# Power.net
KiCad netlist of a schematic drawn in Altium Designer
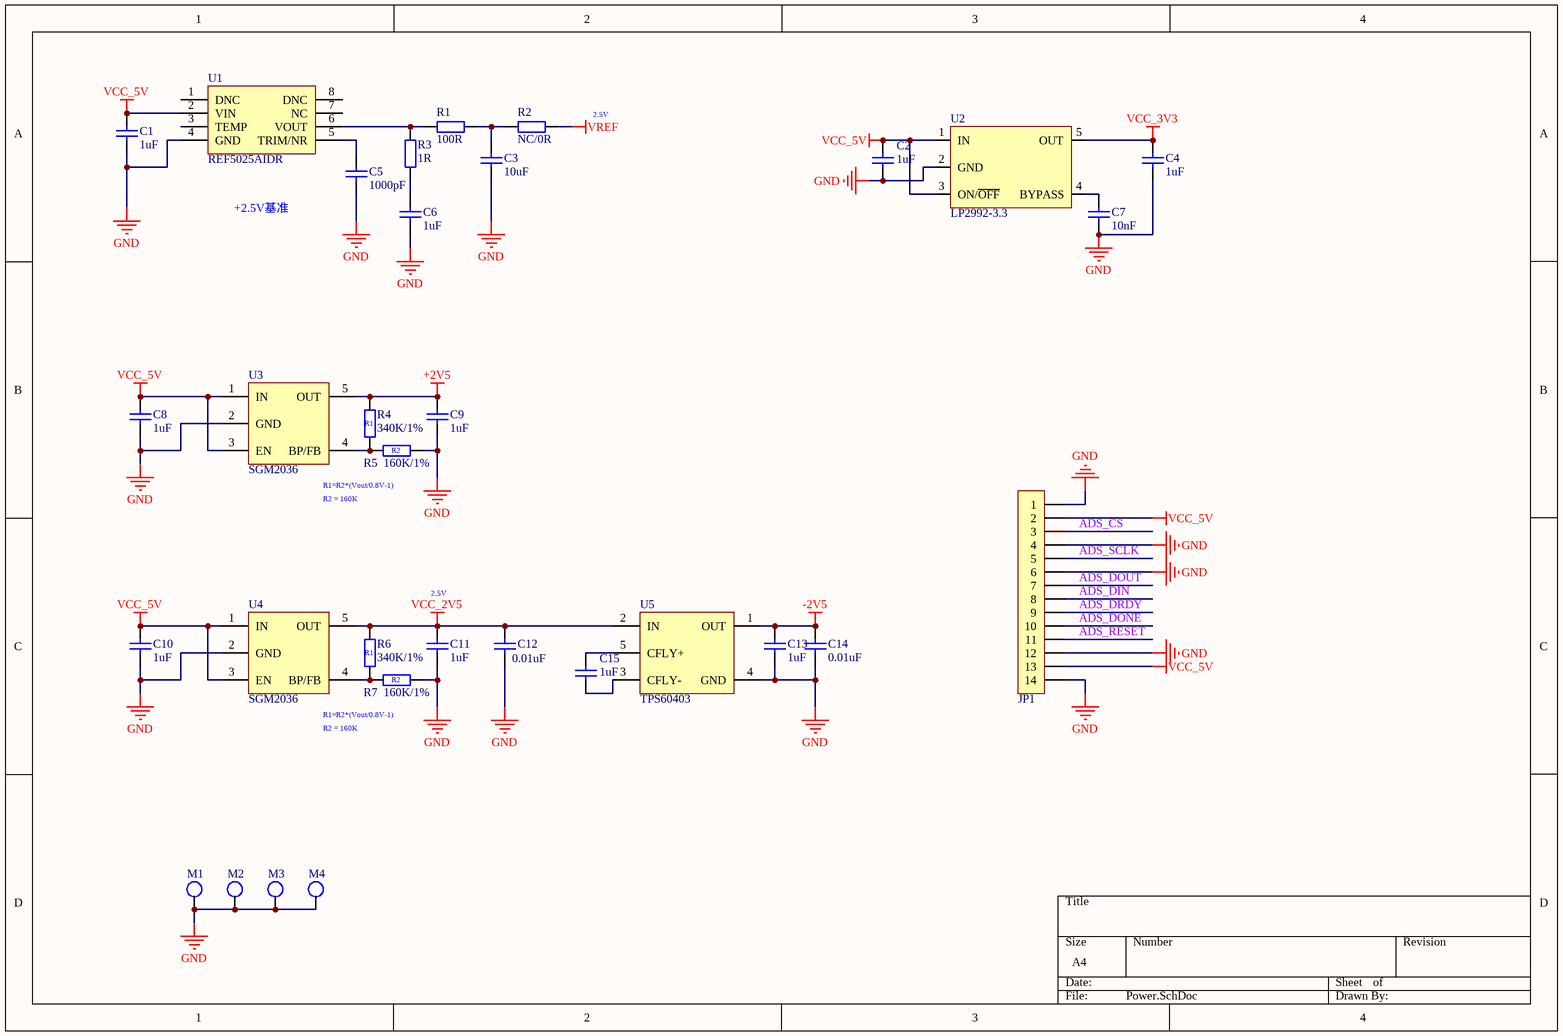
[diagram p0: Power.SchDoc]

(export (version "E")
  (design (tool "Eeschema 10.0.6"))
  (components
    (comp (ref "C1")
      (value "1uF")
      (footprint "C0402_L")
      (description "贴片电容")
      (libsource (lib "0.1 - 电阻-电容-电感-晶振-晶体-磁珠-电位器") (part "C"))
    )
    (comp (ref "C2")
      (value "1uF")
      (footprint "C0402_L")
      (description "贴片电容")
      (libsource (lib "0.1 - 电阻-电容-电感-晶振-晶体-磁珠-电位器") (part "C"))
    )
    (comp (ref "C3")
      (value "10uF")
      (footprint "C0603_L")
      (description "贴片电容")
      (libsource (lib "0.1 - 电阻-电容-电感-晶振-晶体-磁珠-电位器") (part "C"))
    )
    (comp (ref "C4")
      (value "1uF")
      (footprint "C0402_L")
      (description "贴片电容")
      (libsource (lib "0.1 - 电阻-电容-电感-晶振-晶体-磁珠-电位器") (part "C"))
    )
    (comp (ref "C5")
      (value "1000pF")
      (footprint "C0402_L")
      (description "贴片电容")
      (libsource (lib "0.1 - 电阻-电容-电感-晶振-晶体-磁珠-电位器") (part "C"))
    )
    (comp (ref "C6")
      (value "1uF")
      (footprint "C0402_L")
      (description "贴片电容")
      (libsource (lib "0.1 - 电阻-电容-电感-晶振-晶体-磁珠-电位器") (part "C"))
    )
    (comp (ref "C7")
      (value "10nF")
      (footprint "C0402_L")
      (description "贴片电容")
      (libsource (lib "0.1 - 电阻-电容-电感-晶振-晶体-磁珠-电位器") (part "C"))
    )
    (comp (ref "C8")
      (value "1uF")
      (footprint "C0402_L")
      (description "贴片电容")
      (libsource (lib "0.1 - 电阻-电容-电感-晶振-晶体-磁珠-电位器") (part "C"))
    )
    (comp (ref "C9")
      (value "1uF")
      (footprint "C0402_L")
      (description "贴片电容")
      (libsource (lib "0.1 - 电阻-电容-电感-晶振-晶体-磁珠-电位器") (part "C"))
    )
    (comp (ref "C10")
      (value "1uF")
      (footprint "C0402_L")
      (description "贴片电容")
      (libsource (lib "0.1 - 电阻-电容-电感-晶振-晶体-磁珠-电位器") (part "C"))
    )
    (comp (ref "C11")
      (value "1uF")
      (footprint "C0402_L")
      (description "贴片电容")
      (libsource (lib "0.1 - 电阻-电容-电感-晶振-晶体-磁珠-电位器") (part "C"))
    )
    (comp (ref "C12")
      (value "0.01uF")
      (footprint "C0402_L")
      (description "贴片电容")
      (libsource (lib "0.1 - 电阻-电容-电感-晶振-晶体-磁珠-电位器") (part "C"))
    )
    (comp (ref "C13")
      (value "1uF")
      (footprint "C0402_L")
      (description "贴片电容")
      (libsource (lib "0.1 - 电阻-电容-电感-晶振-晶体-磁珠-电位器") (part "C"))
    )
    (comp (ref "C14")
      (value "0.01uF")
      (footprint "C0402_L")
      (description "贴片电容")
      (libsource (lib "0.1 - 电阻-电容-电感-晶振-晶体-磁珠-电位器") (part "C"))
    )
    (comp (ref "C15")
      (value "1uF")
      (footprint "C0402_L")
      (description "贴片电容")
      (libsource (lib "0.1 - 电阻-电容-电感-晶振-晶体-磁珠-电位器") (part "C"))
    )
    (comp (ref "JP1")
      (value "HDR-1X14")
      (footprint "FPC0.5-WT-14P")
      (description "14P接插件")
      (libsource (lib "5.5 - 2.54mm(100mil)连接器(XH2.54)") (part "Header 14"))
    )
    (comp (ref "M1")
      (value "M2")
      (footprint "M2")
      (description "M2孔支撑柱")
      (libsource (lib "USER_Lib") (part "M2系列"))
    )
    (comp (ref "M2")
      (value "M2")
      (footprint "M2")
      (description "M2孔支撑柱")
      (libsource (lib "USER_Lib") (part "M2系列"))
    )
    (comp (ref "M3")
      (value "M2")
      (footprint "M2")
      (description "M2孔支撑柱")
      (libsource (lib "USER_Lib") (part "M2系列"))
    )
    (comp (ref "M4")
      (value "M2")
      (footprint "M2")
      (description "M2孔支撑柱")
      (libsource (lib "USER_Lib") (part "M2系列"))
    )
    (comp (ref "R1")
      (value "100R")
      (footprint "R0402_L")
      (description "贴片电阻")
      (libsource (lib "0.1 - 电阻-电容-电感-晶振-晶体-磁珠-电位器") (part "R"))
    )
    (comp (ref "R2")
      (value "NC/0R")
      (footprint "R0402_L")
      (description "贴片电阻")
      (libsource (lib "0.1 - 电阻-电容-电感-晶振-晶体-磁珠-电位器") (part "R"))
    )
    (comp (ref "R3")
      (value "1R")
      (footprint "R0402_L")
      (description "贴片电阻")
      (libsource (lib "0.1 - 电阻-电容-电感-晶振-晶体-磁珠-电位器") (part "R"))
    )
    (comp (ref "R4")
      (value "340K/1%")
      (footprint "R0402_L")
      (description "贴片电阻")
      (libsource (lib "0.1 - 电阻-电容-电感-晶振-晶体-磁珠-电位器") (part "R"))
    )
    (comp (ref "R5")
      (value "160K/1%")
      (footprint "R0402_L")
      (description "贴片电阻")
      (libsource (lib "0.1 - 电阻-电容-电感-晶振-晶体-磁珠-电位器") (part "R"))
    )
    (comp (ref "R6")
      (value "340K/1%")
      (footprint "R0402_L")
      (description "贴片电阻")
      (libsource (lib "0.1 - 电阻-电容-电感-晶振-晶体-磁珠-电位器") (part "R"))
    )
    (comp (ref "R7")
      (value "160K/1%")
      (footprint "R0402_L")
      (description "贴片电阻")
      (libsource (lib "0.1 - 电阻-电容-电感-晶振-晶体-磁珠-电位器") (part "R"))
    )
    (comp (ref "U1")
      (value "REF5025AIDR")
      (footprint "SOIC-8L")
      (description "3uVpp/V噪声 3ppm/℃漂移 电压基准 0.05%")
      (libsource (lib "USER_Lib") (part "REF5025AIDR"))
    )
    (comp (ref "U2") (value "LP2992-3.3") (footprint "SOT23-5L") (libsource (lib "USER_Lib") (part "LP2992")))
    (comp (ref "U3")
      (value "SGM2036")
      (footprint "SOT23-5L")
      (description "可调LDO")
      (libsource (lib "USER_Lib") (part "SGM2036"))
    )
    (comp (ref "U4")
      (value "SGM2036")
      (footprint "SOT23-5L")
      (description "可调LDO")
      (libsource (lib "USER_Lib") (part "SGM2036"))
    )
    (comp (ref "U5")
      (value "TPS60403")
      (footprint "SOT23-5L")
      (description "非稳压60mA电荷泵电压逆变器")
      (libsource (lib "USER_Lib") (part "TPS6040x"))
    )
  )
  (nets
    (net (code "1") (name "+2V5") (class "Default")
      (node (ref "C9") (pin "2") (pinfunction "2_2") (pintype "passive"))
      (node (ref "R4") (pin "2") (pinfunction "2_2") (pintype "passive"))
      (node (ref "U3") (pin "5") (pinfunction "OUT_5") (pintype "passive"))
    )
    (net (code "2") (name "-2V5") (class "Default")
      (node (ref "C13") (pin "2") (pinfunction "2_2") (pintype "passive"))
      (node (ref "C14") (pin "2") (pinfunction "2_2") (pintype "passive"))
      (node (ref "U5") (pin "1") (pinfunction "OUT_1") (pintype "passive"))
    )
    (net (code "3") (name "/ADS_CS") (class "Default")
      (node (ref "JP1") (pin "3") (pinfunction "3_3") (pintype "passive"))
    )
    (net (code "4") (name "/ADS_DIN") (class "Default")
      (node (ref "JP1") (pin "8") (pinfunction "8_8") (pintype "passive"))
    )
    (net (code "5") (name "/ADS_DONE") (class "Default")
      (node (ref "JP1") (pin "10") (pinfunction "10_10") (pintype "passive"))
    )
    (net (code "6") (name "/ADS_DOUT") (class "Default")
      (node (ref "JP1") (pin "7") (pinfunction "7_7") (pintype "passive"))
    )
    (net (code "7") (name "/ADS_DRDY") (class "Default")
      (node (ref "JP1") (pin "9") (pinfunction "9_9") (pintype "passive"))
    )
    (net (code "8") (name "/ADS_RESET") (class "Default")
      (node (ref "JP1") (pin "11") (pinfunction "11_11") (pintype "passive"))
    )
    (net (code "9") (name "/ADS_SCLK") (class "Default")
      (node (ref "JP1") (pin "5") (pinfunction "5_5") (pintype "passive"))
    )
    (net (code "10") (name "GND") (class "Default")
      (node (ref "C1") (pin "1") (pinfunction "1_1") (pintype "passive"))
      (node (ref "C10") (pin "1") (pinfunction "1_1") (pintype "passive"))
      (node (ref "C11") (pin "1") (pinfunction "1_1") (pintype "passive"))
      (node (ref "C12") (pin "1") (pinfunction "1_1") (pintype "passive"))
      (node (ref "C13") (pin "1") (pinfunction "1_1") (pintype "passive"))
      (node (ref "C14") (pin "1") (pinfunction "1_1") (pintype "passive"))
      (node (ref "C2") (pin "1") (pinfunction "1_1") (pintype "passive"))
      (node (ref "C3") (pin "1") (pinfunction "1_1") (pintype "passive"))
      (node (ref "C4") (pin "1") (pinfunction "1_1") (pintype "passive"))
      (node (ref "C5") (pin "1") (pinfunction "1_1") (pintype "passive"))
      (node (ref "C6") (pin "1") (pinfunction "1_1") (pintype "passive"))
      (node (ref "C7") (pin "1") (pinfunction "1_1") (pintype "passive"))
      (node (ref "C8") (pin "1") (pinfunction "1_1") (pintype "passive"))
      (node (ref "C9") (pin "1") (pinfunction "1_1") (pintype "passive"))
      (node (ref "JP1") (pin "1") (pinfunction "1_1") (pintype "passive"))
      (node (ref "JP1") (pin "12") (pinfunction "12_12") (pintype "passive"))
      (node (ref "JP1") (pin "14") (pinfunction "14_14") (pintype "passive"))
      (node (ref "JP1") (pin "4") (pinfunction "4_4") (pintype "passive"))
      (node (ref "JP1") (pin "6") (pinfunction "6_6") (pintype "passive"))
      (node (ref "M1") (pin "1") (pinfunction "1_1") (pintype "passive"))
      (node (ref "M2") (pin "1") (pinfunction "1_1") (pintype "passive"))
      (node (ref "M3") (pin "1") (pinfunction "1_1") (pintype "passive"))
      (node (ref "M4") (pin "1") (pinfunction "1_1") (pintype "passive"))
      (node (ref "R5") (pin "2") (pinfunction "2_2") (pintype "passive"))
      (node (ref "R7") (pin "2") (pinfunction "2_2") (pintype "passive"))
      (node (ref "U1") (pin "4") (pinfunction "GND_4") (pintype "passive"))
      (node (ref "U2") (pin "2") (pinfunction "GND_2") (pintype "passive"))
      (node (ref "U3") (pin "2") (pinfunction "GND_2") (pintype "passive"))
      (node (ref "U4") (pin "2") (pinfunction "GND_2") (pintype "passive"))
      (node (ref "U5") (pin "4") (pinfunction "GND_4") (pintype "passive"))
    )
    (net (code "11") (name "Net-(C3-Pad2)") (class "Default")
      (node (ref "C3") (pin "2") (pinfunction "2_2") (pintype "passive"))
      (node (ref "R1") (pin "2") (pinfunction "2_2") (pintype "passive"))
      (node (ref "R2") (pin "1") (pinfunction "1_1") (pintype "passive"))
    )
    (net (code "12") (name "Net-(C6-Pad2)") (class "Default")
      (node (ref "C6") (pin "2") (pinfunction "2_2") (pintype "passive"))
      (node (ref "R3") (pin "1") (pinfunction "1_1") (pintype "passive"))
    )
    (net (code "13") (name "Net-(U1-TRIM{slash}NR)") (class "Default")
      (node (ref "C5") (pin "2") (pinfunction "2_2") (pintype "passive"))
      (node (ref "U1") (pin "5") (pinfunction "TRIM/NR_5") (pintype "passive"))
    )
    (net (code "14") (name "Net-(U1-VOUT)") (class "Default")
      (node (ref "R1") (pin "1") (pinfunction "1_1") (pintype "passive"))
      (node (ref "R3") (pin "2") (pinfunction "2_2") (pintype "passive"))
      (node (ref "U1") (pin "6") (pinfunction "VOUT_6") (pintype "passive"))
    )
    (net (code "15") (name "Net-(U2-BYPASS)") (class "Default")
      (node (ref "C7") (pin "2") (pinfunction "2_2") (pintype "passive"))
      (node (ref "U2") (pin "4") (pinfunction "BYPASS_4") (pintype "passive"))
    )
    (net (code "16") (name "Net-(U3-BP{slash}FB)") (class "Default")
      (node (ref "R4") (pin "1") (pinfunction "1_1") (pintype "passive"))
      (node (ref "R5") (pin "1") (pinfunction "1_1") (pintype "passive"))
      (node (ref "U3") (pin "4") (pinfunction "BP/FB_4") (pintype "passive"))
    )
    (net (code "17") (name "Net-(U4-BP{slash}FB)") (class "Default")
      (node (ref "R6") (pin "1") (pinfunction "1_1") (pintype "passive"))
      (node (ref "R7") (pin "1") (pinfunction "1_1") (pintype "passive"))
      (node (ref "U4") (pin "4") (pinfunction "BP/FB_4") (pintype "passive"))
    )
    (net (code "18") (name "Net-(U5-CFLY+)") (class "Default")
      (node (ref "C15") (pin "2") (pinfunction "2_2") (pintype "passive"))
      (node (ref "U5") (pin "5") (pinfunction "CFLY+_5") (pintype "passive"))
    )
    (net (code "19") (name "Net-(U5-CFLY-)") (class "Default")
      (node (ref "C15") (pin "1") (pinfunction "1_1") (pintype "passive"))
      (node (ref "U5") (pin "3") (pinfunction "CFLY-_3") (pintype "passive"))
    )
    (net (code "20") (name "VCC_2V5") (class "Default")
      (node (ref "C11") (pin "2") (pinfunction "2_2") (pintype "passive"))
      (node (ref "C12") (pin "2") (pinfunction "2_2") (pintype "passive"))
      (node (ref "R6") (pin "2") (pinfunction "2_2") (pintype "passive"))
      (node (ref "U4") (pin "5") (pinfunction "OUT_5") (pintype "passive"))
      (node (ref "U5") (pin "2") (pinfunction "IN_2") (pintype "passive"))
    )
    (net (code "21") (name "VCC_3V3") (class "Default")
      (node (ref "C4") (pin "2") (pinfunction "2_2") (pintype "passive"))
      (node (ref "U2") (pin "5") (pinfunction "OUT_5") (pintype "passive"))
    )
    (net (code "22") (name "VCC_5V") (class "Default")
      (node (ref "C1") (pin "2") (pinfunction "2_2") (pintype "passive"))
      (node (ref "C10") (pin "2") (pinfunction "2_2") (pintype "passive"))
      (node (ref "C2") (pin "2") (pinfunction "2_2") (pintype "passive"))
      (node (ref "C8") (pin "2") (pinfunction "2_2") (pintype "passive"))
      (node (ref "JP1") (pin "13") (pinfunction "13_13") (pintype "passive"))
      (node (ref "JP1") (pin "2") (pinfunction "2_2") (pintype "passive"))
      (node (ref "U1") (pin "2") (pinfunction "VIN_2") (pintype "passive"))
      (node (ref "U2") (pin "1") (pinfunction "IN_1") (pintype "passive"))
      (node (ref "U2") (pin "3") (pinfunction "ON/~{OFF}_3") (pintype "passive"))
      (node (ref "U3") (pin "1") (pinfunction "IN_1") (pintype "passive"))
      (node (ref "U3") (pin "3") (pinfunction "EN_3") (pintype "passive"))
      (node (ref "U4") (pin "1") (pinfunction "IN_1") (pintype "passive"))
      (node (ref "U4") (pin "3") (pinfunction "EN_3") (pintype "passive"))
    )
    (net (code "23") (name "VREF") (class "Default")
      (node (ref "R2") (pin "2") (pinfunction "2_2") (pintype "passive"))
    )
    (net (code "24") (name "unconnected-(U1-DNC-Pad1)") (class "Default")
      (node (ref "U1") (pin "1") (pinfunction "DNC_1") (pintype "passive"))
    )
    (net (code "25") (name "unconnected-(U1-DNC-Pad8)") (class "Default")
      (node (ref "U1") (pin "8") (pinfunction "DNC_8") (pintype "passive"))
    )
    (net (code "26") (name "unconnected-(U1-NC-Pad7)") (class "Default")
      (node (ref "U1") (pin "7") (pinfunction "NC_7") (pintype "passive"))
    )
    (net (code "27") (name "unconnected-(U1-TEMP-Pad3)") (class "Default")
      (node (ref "U1") (pin "3") (pinfunction "TEMP_3") (pintype "passive"))
    )
  )
)
